# splitPowerSupply.net
KiCad netlist of a schematic drawn in EAGLE
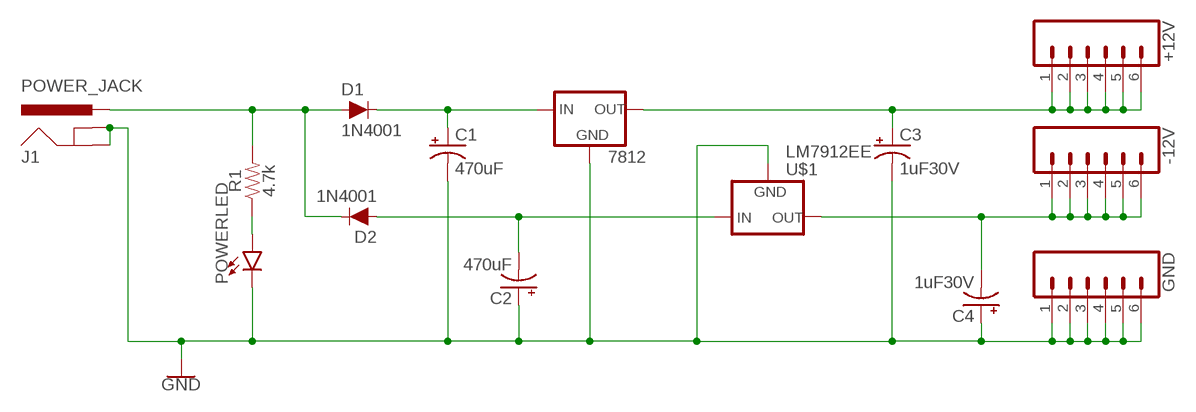
[diagram p0: schematic, sheet 1]

(export (version "E")
  (design (tool "Eeschema 10.0.6"))
  (components
    (comp (ref "+12V")
      (value "CONN_06LONGPADS")
      (footprint "eagle-import:1X06_LONGPADS")
      (libsource (lib "eagle-import") (part "CONN_06LONGPADS"))
    )
    (comp (ref "-12V")
      (value "CONN_06LONGPADS")
      (footprint "eagle-import:1X06_LONGPADS")
      (libsource (lib "eagle-import") (part "CONN_06LONGPADS"))
    )
    (comp (ref "7812")
      (value "V_REG_78XX-TO-220")
      (footprint "eagle-import:TO-220-ALT")
      (libsource (lib "eagle-import") (part "V_REG_78XX-TO-220"))
    )
    (comp (ref "C1")
      (value "470uF")
      (footprint "eagle-import:CPOL-RADIAL-2.5MM-5MM")
      (libsource (lib "eagle-import") (part "10UF-POLAR-RADIAL-2.5MM-25V-20%"))
    )
    (comp (ref "C2")
      (value "470uF")
      (footprint "eagle-import:CPOL-RADIAL-2.5MM-5MM")
      (libsource (lib "eagle-import") (part "10UF-POLAR-RADIAL-2.5MM-25V-20%"))
    )
    (comp (ref "C3")
      (value "1uF30V")
      (footprint "eagle-import:CPOL-RADIAL-2.5MM-5MM")
      (libsource (lib "eagle-import") (part "10UF-POLAR-RADIAL-2.5MM-25V-20%"))
    )
    (comp (ref "C4")
      (value "1uF30V")
      (footprint "eagle-import:CPOL-RADIAL-2.5MM-5MM")
      (libsource (lib "eagle-import") (part "10UF-POLAR-RADIAL-2.5MM-25V-20%"))
    )
    (comp (ref "D1")
      (value "1N4001")
      (footprint "eagle-import:DIODE-1N4001")
      (libsource (lib "eagle-import") (part "DIODE-PTH"))
    )
    (comp (ref "D2")
      (value "1N4001")
      (footprint "eagle-import:DIODE-1N4001")
      (libsource (lib "eagle-import") (part "DIODE-PTH"))
    )
    (comp (ref "GND")
      (value "CONN_06LONGPADS")
      (footprint "eagle-import:1X06_LONGPADS")
      (libsource (lib "eagle-import") (part "CONN_06LONGPADS"))
    )
    (comp (ref "J1")
      (value "POWER_JACK")
      (footprint "eagle-import:POWER_JACK_PTH")
      (libsource (lib "eagle-import") (part "POWER_JACK"))
    )
    (comp (ref "POWERLED")
      (value "LED-3MM-NO_SILK")
      (footprint "eagle-import:LED_3MM-NS")
      (libsource (lib "eagle-import") (part "LED-3MM-NO_SILK"))
    )
    (comp (ref "R1")
      (value "4.7k")
      (footprint "eagle-import:AXIAL-0.3")
      (libsource (lib "eagle-import") (part "1KOHM-HORIZ-1/4W-1%"))
    )
    (comp (ref "U$1")
      (value "LM7912EE")
      (footprint "eagle-import:79XXL")
      (libsource (lib "eagle-import") (part "V_REG_79XX"))
    )
  )
  (nets
    (net (code "1") (name "GND") (class "Default")
      (node (ref "7812") (pin "GND") (pinfunction "GND_GND") (pintype "input"))
      (node (ref "C1") (pin "2") (pinfunction "-_2") (pintype "passive"))
      (node (ref "C2") (pin "1") (pinfunction "+_1") (pintype "passive"))
      (node (ref "C3") (pin "2") (pinfunction "-_2") (pintype "passive"))
      (node (ref "C4") (pin "1") (pinfunction "+_1") (pintype "passive"))
      (node (ref "GND") (pin "1") (pinfunction "1_1") (pintype "passive"))
      (node (ref "GND") (pin "2") (pinfunction "2_2") (pintype "passive"))
      (node (ref "GND") (pin "3") (pinfunction "3_3") (pintype "passive"))
      (node (ref "GND") (pin "4") (pinfunction "4_4") (pintype "passive"))
      (node (ref "GND") (pin "5") (pinfunction "5_5") (pintype "passive"))
      (node (ref "GND") (pin "6") (pinfunction "6_6") (pintype "passive"))
      (node (ref "J1") (pin "GND") (pinfunction "GND_GND") (pintype "bidirectional"))
      (node (ref "J1") (pin "GNDBREAK") (pinfunction "GNDBREAK_GNDBREAK") (pintype "bidirectional"))
      (node (ref "POWERLED") (pin "K") (pinfunction "C_K") (pintype "passive"))
      (node (ref "U$1") (pin "GND") (pinfunction "GND_GND") (pintype "input"))
    )
    (net (code "2") (name "Net-(C1-+)") (class "Default")
      (node (ref "7812") (pin "IN") (pinfunction "IN_IN") (pintype "input"))
      (node (ref "C1") (pin "1") (pinfunction "+_1") (pintype "passive"))
      (node (ref "D1") (pin "C") (pinfunction "C_C") (pintype "passive"))
    )
    (net (code "3") (name "Net-(C2--)") (class "Default")
      (node (ref "C2") (pin "2") (pinfunction "-_2") (pintype "passive"))
      (node (ref "D2") (pin "A") (pinfunction "A_A") (pintype "passive"))
      (node (ref "U$1") (pin "IN") (pinfunction "IN_IN") (pintype "input"))
    )
    (net (code "4") (name "Net-(C3-+)") (class "Default")
      (node (ref "+12V") (pin "1") (pinfunction "1_1") (pintype "passive"))
      (node (ref "+12V") (pin "2") (pinfunction "2_2") (pintype "passive"))
      (node (ref "+12V") (pin "3") (pinfunction "3_3") (pintype "passive"))
      (node (ref "+12V") (pin "4") (pinfunction "4_4") (pintype "passive"))
      (node (ref "+12V") (pin "5") (pinfunction "5_5") (pintype "passive"))
      (node (ref "+12V") (pin "6") (pinfunction "6_6") (pintype "passive"))
      (node (ref "7812") (pin "OUT") (pinfunction "OUT_OUT") (pintype "passive"))
      (node (ref "C3") (pin "1") (pinfunction "+_1") (pintype "passive"))
    )
    (net (code "5") (name "Net-(C4--)") (class "Default")
      (node (ref "-12V") (pin "1") (pinfunction "1_1") (pintype "passive"))
      (node (ref "-12V") (pin "2") (pinfunction "2_2") (pintype "passive"))
      (node (ref "-12V") (pin "3") (pinfunction "3_3") (pintype "passive"))
      (node (ref "-12V") (pin "4") (pinfunction "4_4") (pintype "passive"))
      (node (ref "-12V") (pin "5") (pinfunction "5_5") (pintype "passive"))
      (node (ref "-12V") (pin "6") (pinfunction "6_6") (pintype "passive"))
      (node (ref "C4") (pin "2") (pinfunction "-_2") (pintype "passive"))
      (node (ref "U$1") (pin "OUT") (pinfunction "OUT_OUT") (pintype "passive"))
    )
    (net (code "6") (name "Net-(R1-1)") (class "Default")
      (node (ref "POWERLED") (pin "A") (pinfunction "A_A") (pintype "passive"))
      (node (ref "R1") (pin "P$1") (pinfunction "1_P$1") (pintype "passive"))
    )
    (net (code "7") (name "Net-(R1-2)") (class "Default")
      (node (ref "D1") (pin "A") (pinfunction "A_A") (pintype "passive"))
      (node (ref "D2") (pin "C") (pinfunction "C_C") (pintype "passive"))
      (node (ref "J1") (pin "PWR") (pinfunction "PWR_PWR") (pintype "bidirectional"))
      (node (ref "R1") (pin "P$2") (pinfunction "2_P$2") (pintype "passive"))
    )
  )
)
